# 5VBulkhead.net
KiCad netlist of a schematic drawn in Altium Designer
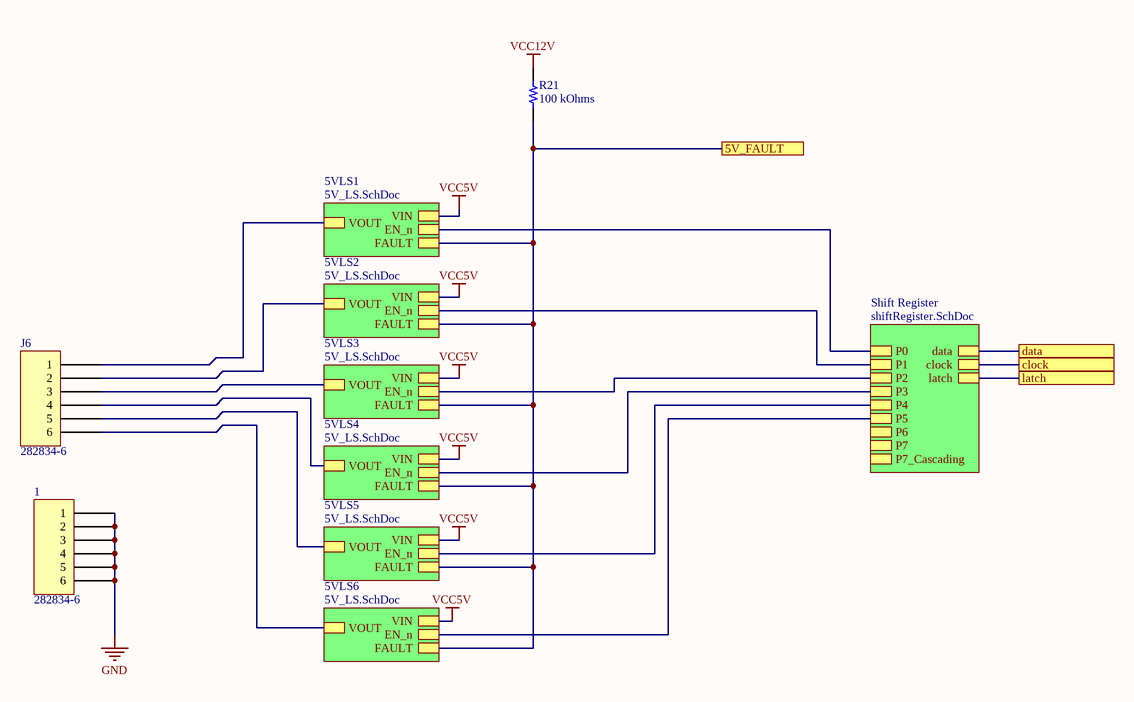
[diagram p0: 5VBulkhead.SchDoc]

(export (version "E")
  (design (tool "Eeschema 10.0.6"))
  (components
    (comp (ref "1")
      (value "282834-6")
      (footprint "TE 282834-6")
      (description "TERM BLK 6P SIDE ENT 2.54MM PCB")
      (fields (field (name "MANUFACTURER") "TE Connectivity AMP Connectors") (field (name "VOLTAGE") "150V"))
      (libsource (lib "Celestial Altium Library - altium_library") (part "6 Pin"))
    )
    (comp (ref "J6")
      (value "282834-6")
      (footprint "TE 282834-6")
      (description "TERM BLK 6P SIDE ENT 2.54MM PCB")
      (fields (field (name "MANUFACTURER") "TE Connectivity AMP Connectors") (field (name "VOLTAGE") "150V"))
      (libsource (lib "Celestial Altium Library - altium_library") (part "6 Pin"))
    )
    (comp (ref "R21")
      (value "100 kOhms")
      (footprint "RES 0603_1608")
      (description "RES 100K OHM 0.1% 1/16W 0603")
      (fields
        (field (name "PART NUMBER") "RNCS0603BKE100K")
        (field (name "MANUFACTURER") "Stackpole Electronics Inc")
      )
      (libsource (lib "Celestial Altium Library - altium_library") (part "Resistor"))
    )
  )
  (nets
    (net (code "1") (name "/5V_FAULT") (class "Default")
      (node (ref "R21") (pin "1") (pinfunction "1_1") (pintype "passive"))
    )
    (net (code "11") (name "/VOUT") (class "Default")
      (node (ref "J6") (pin "1") (pinfunction "1_1") (pintype "passive"))
    )
    (net (code "12") (name "/VOUT_1") (class "Default")
      (node (ref "J6") (pin "2") (pinfunction "2_2") (pintype "passive"))
    )
    (net (code "13") (name "/VOUT_2") (class "Default")
      (node (ref "J6") (pin "3") (pinfunction "3_3") (pintype "passive"))
    )
    (net (code "14") (name "/VOUT_3") (class "Default")
      (node (ref "J6") (pin "4") (pinfunction "4_4") (pintype "passive"))
    )
    (net (code "15") (name "/VOUT_4") (class "Default")
      (node (ref "J6") (pin "5") (pinfunction "5_5") (pintype "passive"))
    )
    (net (code "16") (name "/VOUT_5") (class "Default")
      (node (ref "J6") (pin "6") (pinfunction "6_6") (pintype "passive"))
    )
    (net (code "20") (name "GND") (class "Default")
      (node (ref "1") (pin "1") (pinfunction "1_1") (pintype "passive"))
      (node (ref "1") (pin "2") (pinfunction "2_2") (pintype "passive"))
      (node (ref "1") (pin "3") (pinfunction "3_3") (pintype "passive"))
      (node (ref "1") (pin "4") (pinfunction "4_4") (pintype "passive"))
      (node (ref "1") (pin "5") (pinfunction "5_5") (pintype "passive"))
      (node (ref "1") (pin "6") (pinfunction "6_6") (pintype "passive"))
    )
    (net (code "22") (name "VCC12V") (class "Default")
      (node (ref "R21") (pin "2") (pinfunction "2_2") (pintype "passive"))
    )
  )
)
